# System_Power_Supply.net
KiCad netlist of a schematic drawn in Altium Designer
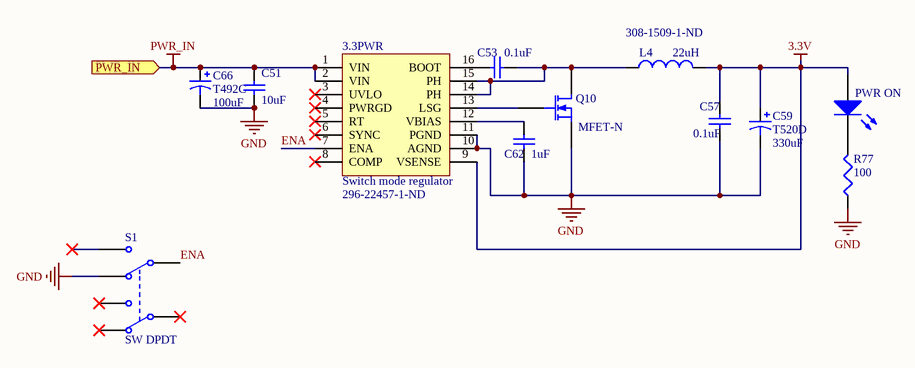
[diagram p0: System Power Supply.SchDoc]

(export (version "E")
  (design (tool "Eeschema 10.0.6"))
  (components
    (comp (ref "3.3PWR")
      (value "Switch mode regulator")
      (footprint "TSOP65P640X120_HS-16N")
      (description "296-22457-1-ND")
      (fields
        (field (name "MANUFACTURER") "Texas Instruments")
        (field (name "MANUFACTURER PART NUMBER") "TPS54356MPWPREP")
        (field (name "SUPPLIER PART NUMBER 1") "296-22457-1-ND")
      )
      (libsource (lib "Components") (part "TPS54356"))
    )
    (comp (ref "C51")
      (value "10uF")
      (footprint "0603_CAP")
      (description "Capacitor")
      (fields (field (name "Comment") "X7R Cap") (field (name "PUBLISHER") "Altium Limited"))
      (libsource (lib "Miscellaneous Devices") (part "Cap"))
    )
    (comp (ref "C53")
      (value "0.1uF")
      (footprint "0603_CAP")
      (description "Capacitor")
      (fields (field (name "Comment") "X7R Cap") (field (name "PUBLISHER") "Altium Limited"))
      (libsource (lib "Miscellaneous Devices") (part "Cap"))
    )
    (comp (ref "C57")
      (value "0.1uF")
      (footprint "0603_CAP")
      (description "Capacitor")
      (fields (field (name "Comment") "X7R Cap") (field (name "PUBLISHER") "Altium Limited"))
      (libsource (lib "Miscellaneous Devices") (part "Cap"))
    )
    (comp (ref "C59")
      (value "T520D")
      (footprint "D")
      (description "Polymer Tantalum Chip Capacitor, T520 Series - KO-CAP Polymer")
      (fields (field (name "ALTIUM_VALUE") "330uF") (field (name "PUBLISHER") "Altium Limited"))
      (libsource (lib "KEMET Chip Capacitor") (part "T520D"))
    )
    (comp (ref "C62")
      (value "1uF")
      (footprint "0603_CAP")
      (description "Capacitor")
      (fields (field (name "Comment") "X7R Cap") (field (name "PUBLISHER") "Altium Limited"))
      (libsource (lib "Miscellaneous Devices") (part "Cap"))
    )
    (comp (ref "C66")
      (value "T492C")
      (footprint "C")
      (description "Solid Tantalum Chip Capacitor, T492 Series - CWR11 Style Per Mil-PRF-55365/8")
      (fields
        (field (name "ALTIUM_VALUE") "100uF")
        (field (name "MANUFACTURER") "Kemet")
        (field (name "MANUFACTURER PART NUMBER") "T491C107K016ZT")
        (field (name "PUBLISHER") "Altium Limited")
      )
      (libsource (lib "KEMET Chip Capacitor") (part "T492C"))
    )
    (comp (ref "L4")
      (value "22uH")
      (footprint "INDM7575X45N")
      (description "Inductor")
      (fields
        (field (name "MANUFACTURER") "SUMIDA AMERICA COMPONENTS INC")
        (field (name "MANUFACTURER PART NUMBER") "CDRH74NP-150MC")
        (field (name "SUPPLIER PART NUMBER 2") "308-1509-1-ND")
        (field (name "PUBLISHER") "Altium Limited")
      )
      (libsource (lib "Miscellaneous Devices") (part "Inductor"))
    )
    (comp (ref "PWR ON")
      (value "LED0")
      (footprint "0603_RES")
      (description "Typical INFRARED GaAs LED")
      (fields (field (name "PUBLISHER") "Altium Limited"))
      (libsource (lib "Miscellaneous Devices") (part "LED0"))
    )
    (comp (ref "Q10")
      (value "MFET-N")
      (footprint "CSD16321Q5")
      (description "N-Channel MOSFET")
      (fields (field (name "PUBLISHER") "Altium Limited"))
      (libsource (lib "Miscellaneous Devices") (part "MOSFET-N"))
    )
    (comp (ref "R77")
      (value "100")
      (footprint "0603_RES")
      (description "Resistor")
      (fields (field (name "Comment") "Rpull") (field (name "PUBLISHER") "Altium Limited"))
      (libsource (lib "Miscellaneous Devices") (part "Res3"))
    )
    (comp (ref "S1")
      (value "SW DPDT")
      (footprint "SPDT")
      (description "Switch")
      (fields
        (field (name "MANUFACTURER") "C&K Components")
        (field (name "MANUFACTURER PART NUMBER") "JS202011SCQN")
        (field (name "PUBLISHER") "Altium Limited")
      )
      (libsource (lib "Miscellaneous Devices") (part "SW DPDT"))
    )
  )
  (nets
    (net (code "1") (name "/ENA") (class "Default")
      (node (ref "3.3PWR") (pin "7") (pinfunction "ENA_7") (pintype "passive"))
      (node (ref "S1") (pin "5") (pinfunction "COMMON2_5") (pintype "passive"))
    )
    (net (code "2") (name "3.3V") (class "Default")
      (node (ref "3.3PWR") (pin "9") (pinfunction "VSENSE_9") (pintype "passive"))
      (node (ref "C57") (pin "2") (pinfunction "2_2") (pintype "passive"))
      (node (ref "C59") (pin "1") (pinfunction "1_1") (pintype "passive"))
      (node (ref "L4") (pin "2") (pinfunction "2_2") (pintype "passive"))
      (node (ref "PWR ON") (pin "1") (pinfunction "A_1") (pintype "passive"))
    )
    (net (code "3") (name "GND") (class "Default")
      (node (ref "3.3PWR") (pin "10") (pinfunction "AGND_10") (pintype "passive"))
      (node (ref "3.3PWR") (pin "11") (pinfunction "PGND_11") (pintype "passive"))
      (node (ref "C51") (pin "1") (pinfunction "1_1") (pintype "passive"))
      (node (ref "C57") (pin "1") (pinfunction "1_1") (pintype "passive"))
      (node (ref "C59") (pin "2") (pinfunction "2_2") (pintype "passive"))
      (node (ref "C62") (pin "2") (pinfunction "2_2") (pintype "passive"))
      (node (ref "C66") (pin "2") (pinfunction "2_2") (pintype "passive"))
      (node (ref "Q10") (pin "3") (pinfunction "S_3") (pintype "passive"))
      (node (ref "R77") (pin "1") (pinfunction "1_1") (pintype "passive"))
      (node (ref "S1") (pin "4") (pinfunction "NC2_4") (pintype "passive"))
    )
    (net (code "4") (name "Net-(3.3PWR-BOOT)") (class "Default")
      (node (ref "3.3PWR") (pin "16") (pinfunction "BOOT_16") (pintype "passive"))
      (node (ref "C53") (pin "2") (pinfunction "2_2") (pintype "passive"))
    )
    (net (code "5") (name "Net-(3.3PWR-LSG)") (class "Default")
      (node (ref "3.3PWR") (pin "13") (pinfunction "LSG_13") (pintype "passive"))
      (node (ref "Q10") (pin "2") (pinfunction "G_2") (pintype "passive"))
    )
    (net (code "6") (name "Net-(3.3PWR-VBIAS)") (class "Default")
      (node (ref "3.3PWR") (pin "12") (pinfunction "VBIAS_12") (pintype "passive"))
      (node (ref "C62") (pin "1") (pinfunction "1_1") (pintype "passive"))
    )
    (net (code "7") (name "Net-(PWR ON-K)") (class "Default")
      (node (ref "PWR ON") (pin "2") (pinfunction "K_2") (pintype "passive"))
      (node (ref "R77") (pin "2") (pinfunction "2_2") (pintype "passive"))
    )
    (net (code "8") (name "Net-(Q10-D)") (class "Default")
      (node (ref "3.3PWR") (pin "14") (pinfunction "PH_14") (pintype "passive"))
      (node (ref "3.3PWR") (pin "15") (pinfunction "PH_15") (pintype "passive"))
      (node (ref "C53") (pin "1") (pinfunction "1_1") (pintype "passive"))
      (node (ref "L4") (pin "1") (pinfunction "1_1") (pintype "passive"))
      (node (ref "Q10") (pin "1") (pinfunction "D_1") (pintype "passive"))
    )
    (net (code "9") (name "PWR_IN") (class "Default")
      (node (ref "3.3PWR") (pin "1") (pinfunction "VIN_1") (pintype "passive"))
      (node (ref "3.3PWR") (pin "2") (pinfunction "VIN_2") (pintype "passive"))
      (node (ref "C51") (pin "2") (pinfunction "2_2") (pintype "passive"))
      (node (ref "C66") (pin "1") (pinfunction "1_1") (pintype "passive"))
    )
    (net (code "10") (name "unconnected-(3.3PWR-COMP-Pad8)") (class "Default")
      (node (ref "3.3PWR") (pin "8") (pinfunction "COMP_8") (pintype "passive+no_connect"))
    )
    (net (code "11") (name "unconnected-(3.3PWR-PWRGD-Pad4)") (class "Default")
      (node (ref "3.3PWR") (pin "4") (pinfunction "PWRGD_4") (pintype "passive+no_connect"))
    )
    (net (code "12") (name "unconnected-(3.3PWR-RT-Pad5)") (class "Default")
      (node (ref "3.3PWR") (pin "5") (pinfunction "RT_5") (pintype "passive+no_connect"))
    )
    (net (code "13") (name "unconnected-(3.3PWR-SYNC-Pad6)") (class "Default")
      (node (ref "3.3PWR") (pin "6") (pinfunction "SYNC_6") (pintype "passive+no_connect"))
    )
    (net (code "14") (name "unconnected-(3.3PWR-UVLO-Pad3)") (class "Default")
      (node (ref "3.3PWR") (pin "3") (pinfunction "UVLO_3") (pintype "passive+no_connect"))
    )
    (net (code "15") (name "unconnected-(S1-COMMON1-Pad1)") (class "Default")
      (node (ref "S1") (pin "1") (pinfunction "COMMON1_1") (pintype "passive+no_connect"))
    )
    (net (code "16") (name "unconnected-(S1-NC1-Pad2)") (class "Default")
      (node (ref "S1") (pin "2") (pinfunction "NC1_2") (pintype "passive+no_connect"))
    )
    (net (code "17") (name "unconnected-(S1-NO1-Pad3)") (class "Default")
      (node (ref "S1") (pin "3") (pinfunction "NO1_3") (pintype "passive+no_connect"))
    )
    (net (code "18") (name "unconnected-(S1-NO2-Pad6)") (class "Default")
      (node (ref "S1") (pin "6") (pinfunction "NO2_6") (pintype "passive+no_connect"))
    )
  )
)
